# Sheet1.net
KiCad netlist of a schematic drawn in Altium Designer
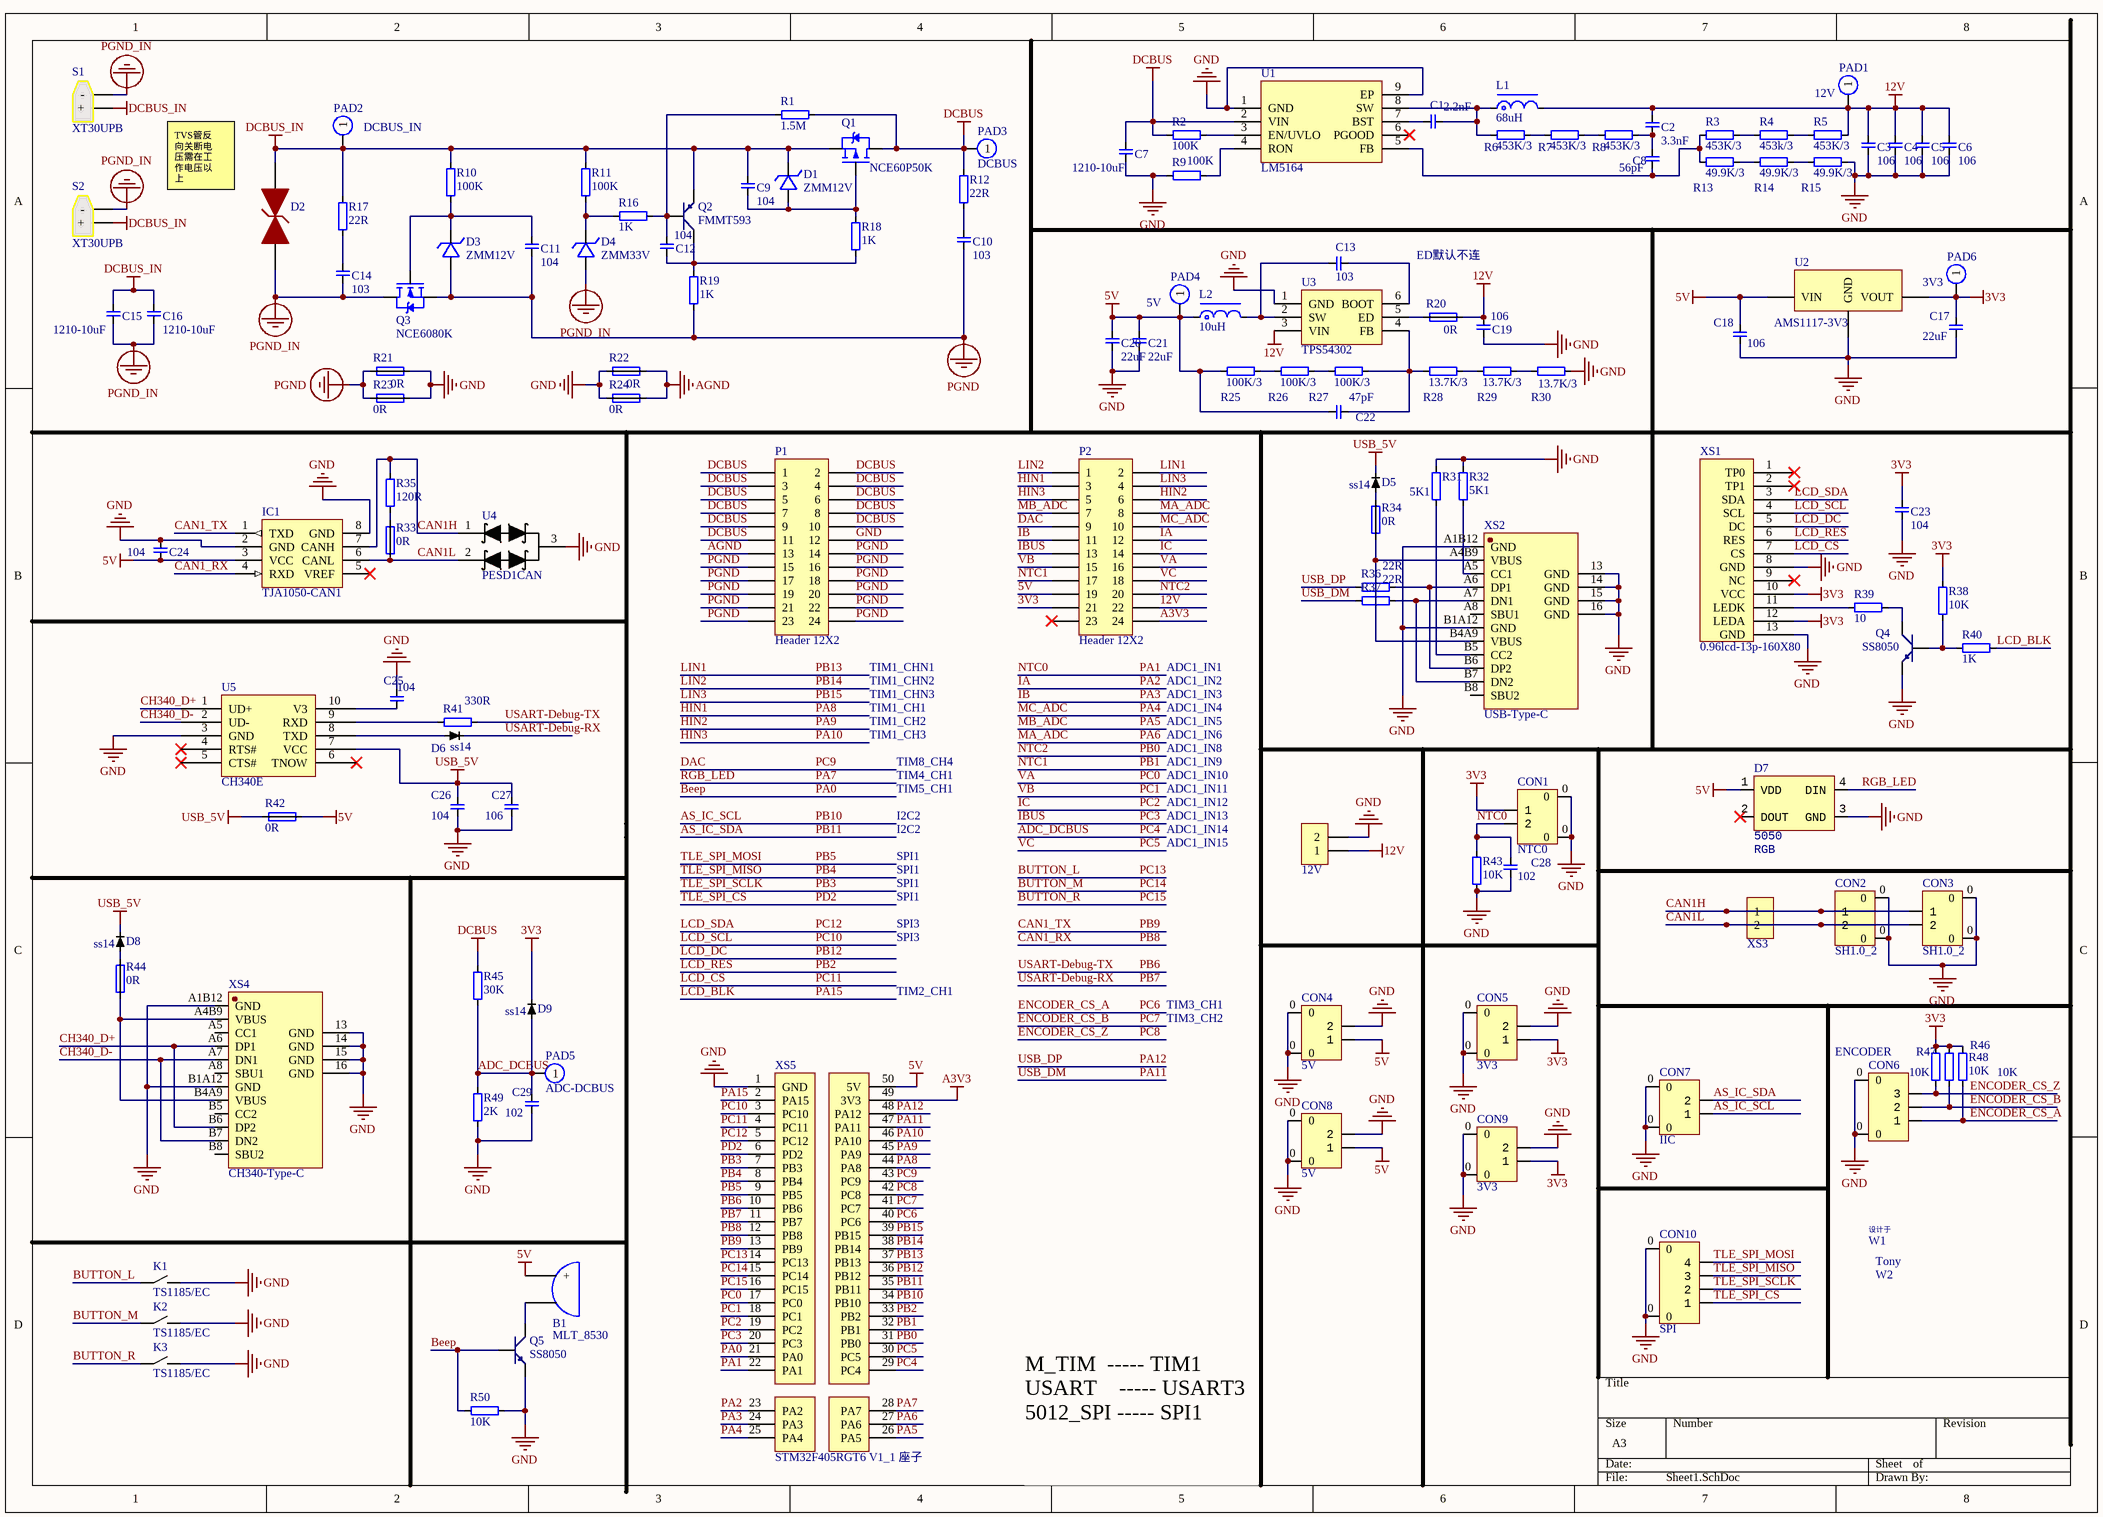
[diagram p0: Sheet1.SchDoc]

(export (version "E")
  (design (tool "Eeschema 10.0.6"))
  (components
    (comp (ref "12V")
      (value "HDR-1X2")
      (footprint "15EDGVM-2P")
      (description "2P接插件")
      (fields (field (name "版权归属") "源创客"))
      (libsource (lib "") (part "Header 2_1"))
    )
    (comp (ref "B1") (value "MLT_8530") (footprint "BEEP-8530") (libsource (lib "基本元件库") (part "Beep")))
    (comp (ref "C1") (value "2.2nF") (footprint "CAP_0603") (libsource (lib "基本元件库") (part "cap")))
    (comp (ref "C2") (value "3.3nF") (footprint "CAP_0603") (libsource (lib "基本元件库") (part "cap")))
    (comp (ref "C3") (value "106") (footprint "CAP_0603") (libsource (lib "基本元件库") (part "cap")))
    (comp (ref "C4") (value "106") (footprint "CAP_0603") (libsource (lib "基本元件库") (part "cap")))
    (comp (ref "C5") (value "106") (footprint "CAP_0603") (libsource (lib "基本元件库") (part "cap")))
    (comp (ref "C6") (value "106") (footprint "CAP_0603") (libsource (lib "基本元件库") (part "cap")))
    (comp (ref "C7") (value "1210-10uF") (footprint "CAP_1210_L") (libsource (lib "基本元件库") (part "cap")))
    (comp (ref "C8") (value "56pF") (footprint "CAP_0603") (libsource (lib "基本元件库") (part "cap")))
    (comp (ref "C9") (value "104") (footprint "CAP_0603") (libsource (lib "基本元件库") (part "cap")))
    (comp (ref "C10") (value "103") (footprint "CAP_0603") (libsource (lib "基本元件库") (part "cap")))
    (comp (ref "C11") (value "104") (footprint "CAP_0603") (libsource (lib "基本元件库") (part "cap")))
    (comp (ref "C12") (value "104") (footprint "CAP_0603") (libsource (lib "基本元件库") (part "cap")))
    (comp (ref "C13") (value "103") (footprint "CAP_0603") (libsource (lib "基本元件库") (part "cap")))
    (comp (ref "C14") (value "103") (footprint "CAP_0603") (libsource (lib "基本元件库") (part "cap")))
    (comp (ref "C15") (value "1210-10uF") (footprint "CAP_1210_L") (libsource (lib "基本元件库") (part "cap")))
    (comp (ref "C16") (value "1210-10uF") (footprint "CAP_1210_L") (libsource (lib "基本元件库") (part "cap")))
    (comp (ref "C17") (value "22uF") (footprint "CAP_0603") (libsource (lib "基本元件库") (part "cap")))
    (comp (ref "C18") (value "106") (footprint "CAP_0603") (libsource (lib "基本元件库") (part "cap")))
    (comp (ref "C19") (value "106") (footprint "CAP_0603") (libsource (lib "基本元件库") (part "cap")))
    (comp (ref "C20") (value "22uF") (footprint "CAP_0603") (libsource (lib "基本元件库") (part "cap")))
    (comp (ref "C21") (value "22uF") (footprint "CAP_0603") (libsource (lib "基本元件库") (part "cap")))
    (comp (ref "C22") (value "47pF") (footprint "CAP_0603") (libsource (lib "基本元件库") (part "cap")))
    (comp (ref "C23") (value "104") (footprint "CAP_0603") (libsource (lib "基本元件库") (part "cap")))
    (comp (ref "C24") (value "104") (footprint "CAP_0603") (libsource (lib "基本元件库") (part "cap")))
    (comp (ref "C25") (value "104") (footprint "CAP_0603") (libsource (lib "基本元件库") (part "cap")))
    (comp (ref "C26") (value "104") (footprint "CAP_0603") (libsource (lib "基本元件库") (part "cap")))
    (comp (ref "C27") (value "106") (footprint "CAP_0603") (libsource (lib "基本元件库") (part "cap")))
    (comp (ref "C28") (value "102") (footprint "CAP_0603") (libsource (lib "基本元件库") (part "cap")))
    (comp (ref "C29") (value "102") (footprint "CAP_0603") (libsource (lib "基本元件库") (part "cap")))
    (comp (ref "CON1")
      (value "NTC0")
      (footprint "PH2.0-LS-2P")
      (description "PH2.0_2 座子")
      (libsource (lib "接插件库") (part "PH2.0_2"))
    )
    (comp (ref "CON2")
      (value "SH1.0_2")
      (footprint "SH1.0 LS 2P")
      (description "SH1.0 座子")
      (libsource (lib "接插件库") (part "SH1.0_2"))
    )
    (comp (ref "CON3")
      (value "SH1.0_2")
      (footprint "SH1.0 LS 2P")
      (description "SH1.0 座子")
      (libsource (lib "接插件库") (part "SH1.0_2"))
    )
    (comp (ref "CON4")
      (value "5V")
      (footprint "XH2.54-LS-2P")
      (description "XH2.54_2 座子")
      (libsource (lib "接插件库") (part "XH2.54_2"))
    )
    (comp (ref "CON5")
      (value "3V3")
      (footprint "ZH1.5-LS-2P")
      (description "ZH1.5_2 座子")
      (libsource (lib "接插件库") (part "ZH1.5_2"))
    )
    (comp (ref "CON6")
      (value "ENCODER")
      (footprint "PH2.0-LS-3P")
      (description "PH2.0 座子")
      (libsource (lib "接插件库") (part "PH2.0_3"))
    )
    (comp (ref "CON7")
      (value "IIC")
      (footprint "PH2.0-LS-2P")
      (description "PH2.0_2 座子")
      (libsource (lib "") (part "PH2.0_2_1"))
    )
    (comp (ref "CON8")
      (value "5V")
      (footprint "XH2.54-LS-2P")
      (description "XH2.54_2 座子")
      (libsource (lib "接插件库") (part "XH2.54_2"))
    )
    (comp (ref "CON9")
      (value "3V3")
      (footprint "ZH1.5-LS-2P")
      (description "ZH1.5_2 座子")
      (libsource (lib "接插件库") (part "ZH1.5_2"))
    )
    (comp (ref "CON10")
      (value "SPI")
      (footprint "SH1.0 LS 4P")
      (description "SH1.0 座子")
      (libsource (lib "接插件库") (part "SH1.0_4"))
    )
    (comp (ref "D1")
      (value "ZMM12V")
      (footprint "LL-34")
      (description "Zener Diodes 稳压二极管")
      (libsource (lib "基本元件库") (part "ZD"))
    )
    (comp (ref "D2")
      (value "SMBJ28CA")
      (footprint "SMB(DO-211AA)")
      (description "瞬态电压抑制二极管(TVS) 钳位二极管")
      (libsource (lib "基本元件库") (part "TVS"))
    )
    (comp (ref "D3")
      (value "ZMM12V")
      (footprint "LL-34")
      (description "Zener Diodes 稳压二极管")
      (libsource (lib "基本元件库") (part "ZD"))
    )
    (comp (ref "D4")
      (value "ZMM33V")
      (footprint "LL-34")
      (description "Zener Diodes 稳压二极管")
      (libsource (lib "基本元件库") (part "ZD"))
    )
    (comp (ref "D5") (value "ss14") (footprint "SOD-323") (libsource (lib "基本元件库") (part "Diode")))
    (comp (ref "D6") (value "ss14") (footprint "SOD-323") (libsource (lib "") (part "Diode_1")))
    (comp (ref "D7")
      (value "RGB")
      (footprint "LED_5050_WS2812B")
      (description "LED")
      (fields (field (name "TYPE") "5050"))
      (libsource (lib "基本元件库") (part "RGB_4WIC"))
    )
    (comp (ref "D8") (value "ss14") (footprint "SOD-323") (libsource (lib "基本元件库") (part "Diode")))
    (comp (ref "D9") (value "ss14") (footprint "SOD-323") (libsource (lib "基本元件库") (part "Diode")))
    (comp (ref "IC1")
      (value "TJA1050-CAN1")
      (footprint "SOP8_N")
      (description "CAN总线收发芯片")
      (fields (field (name "版权归属") "源创客"))
      (libsource (lib "IC") (part "TJA1050"))
    )
    (comp (ref "K1")
      (value "TS1185/EC")
      (footprint "TS-1185EC-X-X-X")
      (description "3*4*2 立贴轻触开关 2Pin/4Pin")
      (libsource (lib "基本元件库") (part "Button-LT-3040"))
    )
    (comp (ref "K2")
      (value "TS1185/EC")
      (footprint "TS-1185EC-X-X-X")
      (description "3*4*2 立贴轻触开关 2Pin/4Pin")
      (libsource (lib "基本元件库") (part "Button-LT-3040"))
    )
    (comp (ref "K3")
      (value "TS1185/EC")
      (footprint "TS-1185EC-X-X-X")
      (description "3*4*2 立贴轻触开关 2Pin/4Pin")
      (libsource (lib "基本元件库") (part "Button-LT-3040"))
    )
    (comp (ref "L1") (value "68uH") (footprint "NR4030") (libsource (lib "基本元件库") (part "INDUCTOR")))
    (comp (ref "L2") (value "10uH") (footprint "NR3015") (libsource (lib "基本元件库") (part "INDUCTOR")))
    (comp (ref "P1")
      (value "Header 12X2")
      (footprint "HDR2X12")
      (description "Header, 12-Pin, Dual row")
      (fields (field (name "PUBLISHER") "Altium Limited"))
      (libsource (lib "Miscellaneous Connectors") (part "Header 12X2"))
    )
    (comp (ref "P2")
      (value "Header 12X2")
      (footprint "HDR2X12")
      (description "Header, 12-Pin, Dual row")
      (fields (field (name "PUBLISHER") "Altium Limited"))
      (libsource (lib "Miscellaneous Connectors") (part "Header 12X2"))
    )
    (comp (ref "PAD1")
      (value "12V")
      (footprint "PAD-1")
      (description "50mil单点焊盘，用于测试")
      (libsource (lib "基本元件库") (part "PAD"))
    )
    (comp (ref "PAD2")
      (value "DCBUS_IN")
      (footprint "PAD-1")
      (description "50mil单点焊盘，用于测试")
      (libsource (lib "基本元件库") (part "PAD"))
    )
    (comp (ref "PAD3")
      (value "DCBUS")
      (footprint "PAD-1")
      (description "50mil单点焊盘，用于测试")
      (libsource (lib "基本元件库") (part "PAD"))
    )
    (comp (ref "PAD4")
      (value "5V")
      (footprint "PAD-1")
      (description "50mil单点焊盘，用于测试")
      (libsource (lib "基本元件库") (part "PAD"))
    )
    (comp (ref "PAD5")
      (value "ADC-DCBUS")
      (footprint "PAD-1")
      (description "50mil单点焊盘，用于测试")
      (libsource (lib "基本元件库") (part "PAD"))
    )
    (comp (ref "PAD6")
      (value "3V3")
      (footprint "PAD-1")
      (description "50mil单点焊盘，用于测试")
      (libsource (lib "基本元件库") (part "PAD"))
    )
    (comp (ref "Q1")
      (value "NCE60P50K")
      (footprint "TO252-2")
      (description "N沟道MOSFIT\r\n-NCE60P50K-TO252-2")
      (libsource (lib "基本元件库") (part "PMOS"))
    )
    (comp (ref "Q2") (value "FMMT593") (footprint "SOT23") (libsource (lib "基本元件库") (part "PNP")))
    (comp (ref "Q3")
      (value "NCE6080K")
      (footprint "TO252-2")
      (description "N沟道MOSFIT\r\n-NCE6080K-TO252-2")
      (libsource (lib "基本元件库") (part "NMOS"))
    )
    (comp (ref "Q4") (value "SS8050") (footprint "SOT23") (libsource (lib "基本元件库") (part "NPN")))
    (comp (ref "Q5") (value "SS8050") (footprint "SOT23") (libsource (lib "基本元件库") (part "NPN")))
    (comp (ref "R1") (value "1.5M") (footprint "RES_0603") (libsource (lib "基本元件库") (part "Res")))
    (comp (ref "R2") (value "100K") (footprint "RES_0603") (libsource (lib "基本元件库") (part "Res")))
    (comp (ref "R3") (value "453K/3") (footprint "RES_0603") (libsource (lib "基本元件库") (part "Res")))
    (comp (ref "R4") (value "453k/3") (footprint "RES_0603") (libsource (lib "基本元件库") (part "Res")))
    (comp (ref "R5") (value "453K/3") (footprint "RES_0603") (libsource (lib "基本元件库") (part "Res")))
    (comp (ref "R6") (value "453K/3") (footprint "RES_0603") (libsource (lib "基本元件库") (part "Res")))
    (comp (ref "R7") (value "453K/3") (footprint "RES_0603") (libsource (lib "基本元件库") (part "Res")))
    (comp (ref "R8") (value "453K/3") (footprint "RES_0603") (libsource (lib "基本元件库") (part "Res")))
    (comp (ref "R9") (value "100K") (footprint "RES_0603") (libsource (lib "基本元件库") (part "Res")))
    (comp (ref "R10") (value "100K") (footprint "RES_0603") (libsource (lib "基本元件库") (part "Res")))
    (comp (ref "R11") (value "100K") (footprint "RES_0603") (libsource (lib "基本元件库") (part "Res")))
    (comp (ref "R12") (value "22R") (footprint "RES_0603") (libsource (lib "基本元件库") (part "Res")))
    (comp (ref "R13") (value "49.9K/3") (footprint "RES_0603") (libsource (lib "基本元件库") (part "Res")))
    (comp (ref "R14") (value "49.9K/3") (footprint "RES_0603") (libsource (lib "基本元件库") (part "Res")))
    (comp (ref "R15") (value "49.9K/3") (footprint "RES_0603") (libsource (lib "基本元件库") (part "Res")))
    (comp (ref "R16") (value "1K") (footprint "RES_0603") (libsource (lib "基本元件库") (part "Res")))
    (comp (ref "R17") (value "22R") (footprint "RES_0603") (libsource (lib "基本元件库") (part "Res")))
    (comp (ref "R18") (value "1K") (footprint "RES_0603") (libsource (lib "基本元件库") (part "Res")))
    (comp (ref "R19") (value "1K") (footprint "RES_0603") (libsource (lib "基本元件库") (part "Res")))
    (comp (ref "R20") (value "0R") (footprint "RES_0805-SHORT") (libsource (lib "基本元件库") (part "Res-SHORT")))
    (comp (ref "R21") (value "0R") (footprint "RES_0805-SHORT") (libsource (lib "基本元件库") (part "Res-SHORT")))
    (comp (ref "R22") (value "0R") (footprint "RES_0805-SHORT") (libsource (lib "基本元件库") (part "Res-SHORT")))
    (comp (ref "R23") (value "0R") (footprint "RES_0805-SHORT") (libsource (lib "基本元件库") (part "Res-SHORT")))
    (comp (ref "R24") (value "0R") (footprint "RES_0805-SHORT") (libsource (lib "基本元件库") (part "Res-SHORT")))
    (comp (ref "R25") (value "100K/3") (footprint "RES_0603") (libsource (lib "基本元件库") (part "Res")))
    (comp (ref "R26") (value "100K/3") (footprint "RES_0603") (libsource (lib "基本元件库") (part "Res")))
    (comp (ref "R27") (value "100K/3") (footprint "RES_0603") (libsource (lib "基本元件库") (part "Res")))
    (comp (ref "R28") (value "13.7K/3") (footprint "RES_0603") (libsource (lib "基本元件库") (part "Res")))
    (comp (ref "R29") (value "13.7K/3") (footprint "RES_0603") (libsource (lib "基本元件库") (part "Res")))
    (comp (ref "R30") (value "13.7K/3") (footprint "RES_0603") (libsource (lib "基本元件库") (part "Res")))
    (comp (ref "R31") (value "5K1") (footprint "RES_0603") (libsource (lib "基本元件库") (part "Res")))
    (comp (ref "R32") (value "5K1") (footprint "RES_0603") (libsource (lib "基本元件库") (part "Res")))
    (comp (ref "R33") (value "0R") (footprint "RES_0805-SHORT") (libsource (lib "基本元件库") (part "Res-SHORT")))
    (comp (ref "R34") (value "0R") (footprint "RES_0805-SHORT") (libsource (lib "基本元件库") (part "Res-SHORT")))
    (comp (ref "R35") (value "120R") (footprint "RES_0603") (libsource (lib "基本元件库") (part "Res")))
    (comp (ref "R36") (value "22R") (footprint "RES_0603") (libsource (lib "基本元件库") (part "Res")))
    (comp (ref "R37") (value "22R") (footprint "RES_0603") (libsource (lib "基本元件库") (part "Res")))
    (comp (ref "R38") (value "10K") (footprint "RES_0603") (libsource (lib "基本元件库") (part "Res")))
    (comp (ref "R39") (value "10") (footprint "RES_0603") (libsource (lib "基本元件库") (part "Res")))
    (comp (ref "R40") (value "1K") (footprint "RES_0603") (libsource (lib "基本元件库") (part "Res")))
    (comp (ref "R41") (value "330R") (footprint "RES_0603") (libsource (lib "基本元件库") (part "Res")))
    (comp (ref "R42") (value "0R") (footprint "RES_0805-SHORT") (libsource (lib "基本元件库") (part "Res-SHORT")))
    (comp (ref "R43") (value "10K") (footprint "RES_0603") (libsource (lib "基本元件库") (part "Res")))
    (comp (ref "R44") (value "0R") (footprint "RES_0805-SHORT") (libsource (lib "基本元件库") (part "Res-SHORT")))
    (comp (ref "R45") (value "30K") (footprint "RES_0603") (libsource (lib "基本元件库") (part "Res")))
    (comp (ref "R46") (value "10K") (footprint "RES_0603") (libsource (lib "基本元件库") (part "Res")))
    (comp (ref "R47") (value "10K") (footprint "RES_0603") (libsource (lib "基本元件库") (part "Res")))
    (comp (ref "R48") (value "10K") (footprint "RES_0603") (libsource (lib "基本元件库") (part "Res")))
    (comp (ref "R49") (value "2K") (footprint "RES_0603") (libsource (lib "基本元件库") (part "Res")))
    (comp (ref "R50") (value "10K") (footprint "RES_0603") (libsource (lib "基本元件库") (part "Res")))
    (comp (ref "S1")
      (value "XT30UPB")
      (footprint "XT30UPB-M")
      (description "XT30UPB-I/O")
      (libsource (lib "SOURCE") (part "XT30UPB"))
    )
    (comp (ref "S2")
      (value "XT30UPB")
      (footprint "XT30UPB-F")
      (description "XT30UPB-I/O")
      (libsource (lib "SOURCE") (part "XT30UPB"))
    )
    (comp (ref "U1")
      (value "LM5164")
      (footprint "SOP-8")
      (description "DC-DC芯片")
      (libsource (lib "SOURCE") (part "LM5164"))
    )
    (comp (ref "U2") (value "AMS1117-3V3") (footprint "SOT223") (libsource (lib "SOURCE") (part "AMS1117")))
    (comp (ref "U3")
      (value "TPS54302")
      (footprint "SOT23-6")
      (description "12V稳压5VDCDC")
      (libsource (lib "SOURCE") (part "TPS54302"))
    )
    (comp (ref "U4")
      (value "PESD1CAN")
      (footprint "SOT23-3")
      (description "CAN过压保护,放于外部接口端")
      (libsource (lib "IC") (part "PESD1CAN"))
    )
    (comp (ref "U5")
      (value "CH340E")
      (footprint "MSOP10")
      (description "USB转串口 无外置晶振")
      (libsource (lib "IC") (part "CH340E"))
    )
    (comp (ref "W1") (value "设计于") (footprint "designed by（430-70）") (libsource (lib "丝印库") (part "设计于")))
    (comp (ref "W2") (value "Tony") (footprint "Tony_2(200-70)") (libsource (lib "丝印库") (part "Tony")))
    (comp (ref "XS1")
      (value "0.96lcd-13p-160X80")
      (footprint "LCD 0.96-13p")
      (description "焊接屏幕")
      (libsource (lib "第一次绘制库") (part "0.96lcd-13p"))
    )
    (comp (ref "XS2")
      (value "USB-Type-C")
      (footprint "TypeC-304-16BCP")
      (libsource (lib "接插件库") (part "Type-C母口"))
    )
    (comp (ref "XS3")
      (value "HDR-1X2")
      (footprint "15EDGVM-2P")
      (description "2P接插件")
      (fields (field (name "版权归属") "源创客"))
      (libsource (lib "接插件库") (part "Header 2"))
    )
    (comp (ref "XS4")
      (value "CH340-Type-C")
      (footprint "TypeC-304-16BCP")
      (libsource (lib "接插件库") (part "Type-C母口"))
    )
    (comp (ref "XS5")
      (value "STM32F405RGT6 V1_1 座子")
      (footprint "STM32F405RGT6 V1_1座子")
      (libsource (lib "第一次绘制库") (part "STM32F405RGT6 V1_1 座子"))
    )
  )
  (nets
    (net (code "1") (name "/ADC_DCBUS") (class "Default")
      (node (ref "C29") (pin "2") (pinfunction "2_2") (pintype "passive"))
      (node (ref "D9") (pin "1") (pintype "passive"))
      (node (ref "PAD5") (pin "1") (pinfunction "1_1") (pintype "passive"))
      (node (ref "R45") (pin "1") (pinfunction "1_1") (pintype "passive"))
      (node (ref "R49") (pin "2") (pinfunction "2_2") (pintype "passive"))
      (node (ref "XS5") (pin "29") (pinfunction "PC4_29") (pintype "passive"))
    )
    (net (code "2") (name "/AS_IC_SCL") (class "Default")
      (node (ref "CON7") (pin "1") (pinfunction "1_1") (pintype "passive"))
      (node (ref "XS5") (pin "34") (pinfunction "PB10_34") (pintype "passive"))
    )
    (net (code "3") (name "/AS_IC_SDA") (class "Default")
      (node (ref "CON7") (pin "2") (pinfunction "2_2") (pintype "passive"))
      (node (ref "XS5") (pin "35") (pinfunction "PB11_35") (pintype "passive"))
    )
    (net (code "4") (name "/BUTTON_L") (class "Default")
      (node (ref "K1") (pin "1") (pinfunction "1_1") (pintype "passive"))
      (node (ref "XS5") (pin "14") (pinfunction "PC13_14") (pintype "passive"))
    )
    (net (code "5") (name "/BUTTON_M") (class "Default")
      (node (ref "K2") (pin "1") (pinfunction "1_1") (pintype "passive"))
      (node (ref "XS5") (pin "15") (pinfunction "PC14_15") (pintype "passive"))
    )
    (net (code "6") (name "/BUTTON_R") (class "Default")
      (node (ref "K3") (pin "1") (pinfunction "1_1") (pintype "passive"))
      (node (ref "XS5") (pin "16") (pinfunction "PC15_16") (pintype "passive"))
    )
    (net (code "7") (name "/Beep") (class "Default")
      (node (ref "Q5") (pin "1") (pinfunction "B_1") (pintype "passive"))
      (node (ref "R50") (pin "2") (pinfunction "2_2") (pintype "passive"))
      (node (ref "XS5") (pin "21") (pinfunction "PA0_21") (pintype "passive"))
    )
    (net (code "8") (name "/CAN1H") (class "Default")
      (node (ref "CON2") (pin "1") (pinfunction "1_1") (pintype "passive"))
      (node (ref "CON3") (pin "1") (pinfunction "1_1") (pintype "passive"))
      (node (ref "IC1") (pin "7") (pinfunction "CANH_7") (pintype "passive"))
      (node (ref "R35") (pin "2") (pinfunction "2_2") (pintype "passive"))
      (node (ref "U4") (pin "1") (pinfunction "1_1") (pintype "passive"))
      (node (ref "XS3") (pin "1") (pinfunction "1_1") (pintype "passive"))
    )
    (net (code "9") (name "/CAN1L") (class "Default")
      (node (ref "CON2") (pin "2") (pinfunction "2_2") (pintype "passive"))
      (node (ref "CON3") (pin "2") (pinfunction "2_2") (pintype "passive"))
      (node (ref "IC1") (pin "6") (pinfunction "CANL_6") (pintype "passive"))
      (node (ref "R33") (pin "2") (pinfunction "2_2") (pintype "passive"))
      (node (ref "U4") (pin "2") (pinfunction "2_2") (pintype "passive"))
      (node (ref "XS3") (pin "2") (pinfunction "2_2") (pintype "passive"))
    )
    (net (code "10") (name "/CAN1_RX") (class "Default")
      (node (ref "IC1") (pin "4") (pinfunction "RXD_4") (pintype "input"))
      (node (ref "XS5") (pin "12") (pinfunction "PB8_12") (pintype "passive"))
    )
    (net (code "11") (name "/CAN1_TX") (class "Default")
      (node (ref "IC1") (pin "1") (pinfunction "TXD_1") (pintype "output"))
      (node (ref "XS5") (pin "13") (pinfunction "PB9_13") (pintype "passive"))
    )
    (net (code "12") (name "/CH340_D+") (class "Default")
      (node (ref "U5") (pin "1") (pinfunction "UD+_1") (pintype "passive"))
      (node (ref "XS4") (pin "A6") (pinfunction "DP1_A6") (pintype "passive"))
      (node (ref "XS4") (pin "B6") (pinfunction "DP2_B6") (pintype "passive"))
    )
    (net (code "13") (name "/CH340_D-") (class "Default")
      (node (ref "U5") (pin "2") (pinfunction "UD-_2") (pintype "passive"))
      (node (ref "XS4") (pin "A7") (pinfunction "DN1_A7") (pintype "passive"))
      (node (ref "XS4") (pin "B7") (pinfunction "DN2_B7") (pintype "passive"))
    )
    (net (code "14") (name "/DAC") (class "Default")
      (node (ref "P2") (pin "9") (pinfunction "9_9") (pintype "passive"))
      (node (ref "XS5") (pin "43") (pinfunction "PC9_43") (pintype "passive"))
    )
    (net (code "15") (name "/ENCODER_CS_A") (class "Default")
      (node (ref "CON6") (pin "1") (pinfunction "1_1") (pintype "passive"))
      (node (ref "R48") (pin "2") (pinfunction "2_2") (pintype "passive"))
      (node (ref "XS5") (pin "40") (pinfunction "PC6_40") (pintype "passive"))
    )
    (net (code "16") (name "/ENCODER_CS_B") (class "Default")
      (node (ref "CON6") (pin "2") (pinfunction "2_2") (pintype "passive"))
      (node (ref "R46") (pin "2") (pinfunction "2_2") (pintype "passive"))
      (node (ref "XS5") (pin "41") (pinfunction "PC7_41") (pintype "passive"))
    )
    (net (code "17") (name "/ENCODER_CS_Z") (class "Default")
      (node (ref "CON6") (pin "3") (pinfunction "3_3") (pintype "passive"))
      (node (ref "R47") (pin "2") (pinfunction "2_2") (pintype "passive"))
      (node (ref "XS5") (pin "42") (pinfunction "PC8_42") (pintype "passive"))
    )
    (net (code "18") (name "/HIN1") (class "Default")
      (node (ref "P2") (pin "3") (pinfunction "3_3") (pintype "passive"))
      (node (ref "XS5") (pin "44") (pinfunction "PA8_44") (pintype "passive"))
    )
    (net (code "19") (name "/HIN2") (class "Default")
      (node (ref "P2") (pin "6") (pinfunction "6_6") (pintype "passive"))
      (node (ref "XS5") (pin "45") (pinfunction "PA9_45") (pintype "passive"))
    )
    (net (code "20") (name "/HIN3") (class "Default")
      (node (ref "P2") (pin "5") (pinfunction "5_5") (pintype "passive"))
      (node (ref "XS5") (pin "46") (pinfunction "PA10_46") (pintype "passive"))
    )
    (net (code "21") (name "/IA") (class "Default")
      (node (ref "P2") (pin "12") (pinfunction "12_12") (pintype "passive"))
      (node (ref "XS5") (pin "23") (pinfunction "PA2_23") (pintype "passive"))
    )
    (net (code "22") (name "/IB") (class "Default")
      (node (ref "P2") (pin "11") (pinfunction "11_11") (pintype "passive"))
      (node (ref "XS5") (pin "24") (pinfunction "PA3_24") (pintype "passive"))
    )
    (net (code "23") (name "/IBUS") (class "Default")
      (node (ref "P2") (pin "13") (pinfunction "13_13") (pintype "passive"))
      (node (ref "XS5") (pin "20") (pinfunction "PC3_20") (pintype "passive"))
    )
    (net (code "24") (name "/IC") (class "Default")
      (node (ref "P2") (pin "14") (pinfunction "14_14") (pintype "passive"))
      (node (ref "XS5") (pin "19") (pinfunction "PC2_19") (pintype "passive"))
    )
    (net (code "25") (name "/LCD_BLK") (class "Default")
      (node (ref "R40") (pin "2") (pinfunction "2_2") (pintype "passive"))
      (node (ref "XS5") (pin "2") (pinfunction "PA15_2") (pintype "passive"))
    )
    (net (code "26") (name "/LCD_CS") (class "Default")
      (node (ref "XS1") (pin "7") (pinfunction "CS_7") (pintype "passive"))
      (node (ref "XS5") (pin "4") (pinfunction "PC11_4") (pintype "passive"))
    )
    (net (code "27") (name "/LCD_DC") (class "Default")
      (node (ref "XS1") (pin "5") (pinfunction "DC_5") (pintype "passive"))
      (node (ref "XS5") (pin "36") (pinfunction "PB12_36") (pintype "passive"))
    )
    (net (code "28") (name "/LCD_RES") (class "Default")
      (node (ref "XS1") (pin "6") (pinfunction "RES_6") (pintype "passive"))
      (node (ref "XS5") (pin "33") (pinfunction "PB2_33") (pintype "passive"))
    )
    (net (code "29") (name "/LCD_SCL") (class "Default")
      (node (ref "XS1") (pin "4") (pinfunction "SCL_4") (pintype "passive"))
      (node (ref "XS5") (pin "3") (pinfunction "PC10_3") (pintype "passive"))
    )
    (net (code "30") (name "/LCD_SDA") (class "Default")
      (node (ref "XS1") (pin "3") (pinfunction "SDA_3") (pintype "passive"))
      (node (ref "XS5") (pin "5") (pinfunction "PC12_5") (pintype "passive"))
    )
    (net (code "31") (name "/LIN1") (class "Default")
      (node (ref "P2") (pin "2") (pinfunction "2_2") (pintype "passive"))
      (node (ref "XS5") (pin "37") (pinfunction "PB13_37") (pintype "passive"))
    )
    (net (code "32") (name "/LIN2") (class "Default")
      (node (ref "P2") (pin "1") (pinfunction "1_1") (pintype "passive"))
      (node (ref "XS5") (pin "38") (pinfunction "PB14_38") (pintype "passive"))
    )
    (net (code "33") (name "/LIN3") (class "Default")
      (node (ref "P2") (pin "4") (pinfunction "4_4") (pintype "passive"))
      (node (ref "XS5") (pin "39") (pinfunction "PB15_39") (pintype "passive"))
    )
    (net (code "34") (name "/MA_ADC") (class "Default")
      (node (ref "P2") (pin "8") (pinfunction "8_8") (pintype "passive"))
      (node (ref "XS5") (pin "27") (pinfunction "PA6_27") (pintype "passive"))
    )
    (net (code "35") (name "/MB_ADC") (class "Default")
      (node (ref "P2") (pin "7") (pinfunction "7_7") (pintype "passive"))
      (node (ref "XS5") (pin "26") (pinfunction "PA5_26") (pintype "passive"))
    )
    (net (code "36") (name "/MC_ADC") (class "Default")
      (node (ref "P2") (pin "10") (pinfunction "10_10") (pintype "passive"))
      (node (ref "XS5") (pin "25") (pinfunction "PA4_25") (pintype "passive"))
    )
    (net (code "37") (name "/NTC0") (class "Default")
      (node (ref "C28") (pin "2") (pinfunction "2_2") (pintype "passive"))
      (node (ref "CON1") (pin "2") (pinfunction "2_2") (pintype "passive"))
      (node (ref "R43") (pin "1") (pinfunction "1_1") (pintype "passive"))
      (node (ref "XS5") (pin "22") (pinfunction "PA1_22") (pintype "passive"))
    )
    (net (code "38") (name "/NTC1") (class "Default")
      (node (ref "P2") (pin "17") (pinfunction "17_17") (pintype "passive"))
      (node (ref "XS5") (pin "32") (pinfunction "PB1_32") (pintype "passive"))
    )
    (net (code "39") (name "/NTC2") (class "Default")
      (node (ref "P2") (pin "20") (pinfunction "20_20") (pintype "passive"))
      (node (ref "XS5") (pin "31") (pinfunction "PB0_31") (pintype "passive"))
    )
    (net (code "40") (name "/PA7") (class "Default")
      (node (ref "D7") (pin "4") (pinfunction "DIN_4") (pintype "passive"))
      (node (ref "XS5") (pin "28") (pinfunction "PA7_28") (pintype "passive"))
    )
    (net (code "41") (name "/PA11") (class "Default")
      (node (ref "R37") (pin "1") (pinfunction "1_1") (pintype "passive"))
      (node (ref "XS5") (pin "47") (pinfunction "PA11_47") (pintype "passive"))
    )
    (net (code "42") (name "/PA12") (class "Default")
      (node (ref "R36") (pin "1") (pinfunction "1_1") (pintype "passive"))
      (node (ref "XS5") (pin "48") (pinfunction "PA12_48") (pintype "passive"))
    )
    (net (code "43") (name "/PB3") (class "Default")
      (node (ref "CON10") (pin "2") (pinfunction "2_2") (pintype "passive"))
      (node (ref "XS5") (pin "7") (pinfunction "PB3_7") (pintype "passive"))
    )
    (net (code "44") (name "/PB4") (class "Default")
      (node (ref "CON10") (pin "3") (pinfunction "3_3") (pintype "passive"))
      (node (ref "XS5") (pin "8") (pinfunction "PB4_8") (pintype "passive"))
    )
    (net (code "45") (name "/PB5") (class "Default")
      (node (ref "CON10") (pin "4") (pinfunction "4_4") (pintype "passive"))
      (node (ref "XS5") (pin "9") (pinfunction "PB5_9") (pintype "passive"))
    )
    (net (code "46") (name "/PB6") (class "Default")
      (node (ref "R41") (pin "2") (pinfunction "2_2") (pintype "passive"))
      (node (ref "XS5") (pin "10") (pinfunction "PB6_10") (pintype "passive"))
    )
    (net (code "47") (name "/PB7") (class "Default")
      (node (ref "D6") (pin "1") (pintype "passive"))
      (node (ref "XS5") (pin "11") (pinfunction "PB7_11") (pintype "passive"))
    )
    (net (code "48") (name "/PC0") (class "Default")
      (node (ref "P2") (pin "16") (pinfunction "16_16") (pintype "passive"))
      (node (ref "XS5") (pin "17") (pinfunction "PC0_17") (pintype "passive"))
    )
    (net (code "49") (name "/PC1") (class "Default")
      (node (ref "P2") (pin "15") (pinfunction "15_15") (pintype "passive"))
      (node (ref "XS5") (pin "18") (pinfunction "PC1_18") (pintype "passive"))
    )
    (net (code "50") (name "/PC5") (class "Default")
      (node (ref "P2") (pin "18") (pinfunction "18_18") (pintype "passive"))
      (node (ref "XS5") (pin "30") (pinfunction "PC5_30") (pintype "passive"))
    )
    (net (code "51") (name "/PD2") (class "Default")
      (node (ref "CON10") (pin "1") (pinfunction "1_1") (pintype "passive"))
      (node (ref "XS5") (pin "6") (pinfunction "PD2_6") (pintype "passive"))
    )
    (net (code "52") (name "3V3") (class "Default")
      (node (ref "C17") (pin "2") (pinfunction "2_2") (pintype "passive"))
      (node (ref "C23") (pin "2") (pinfunction "2_2") (pintype "passive"))
      (node (ref "CON1") (pin "1") (pinfunction "1_1") (pintype "passive"))
      (node (ref "CON5") (pin "1") (pinfunction "1_1") (pintype "passive"))
      (node (ref "CON9") (pin "1") (pinfunction "1_1") (pintype "passive"))
      (node (ref "D9") (pin "2") (pintype "passive"))
      (node (ref "P2") (pin "21") (pinfunction "21_21") (pintype "passive"))
      (node (ref "PAD6") (pin "1") (pinfunction "1_1") (pintype "passive"))
      (node (ref "R38") (pin "1") (pinfunction "1_1") (pintype "passive"))
      (node (ref "R46") (pin "1") (pinfunction "1_1") (pintype "passive"))
      (node (ref "R47") (pin "1") (pinfunction "1_1") (pintype "passive"))
      (node (ref "R48") (pin "1") (pinfunction "1_1") (pintype "passive"))
      (node (ref "U2") (pin "2") (pinfunction "VOUT_2") (pintype "passive"))
      (node (ref "XS1") (pin "10") (pinfunction "VCC_10") (pintype "passive"))
      (node (ref "XS1") (pin "12") (pinfunction "LEDA_12") (pintype "passive"))
    )
    (net (code "53") (name "5V") (class "Default")
      (node (ref "B1") (pin "1") (pinfunction "+_1") (pintype "passive"))
      (node (ref "C18") (pin "2") (pinfunction "2_2") (pintype "passive"))
      (node (ref "C20") (pin "1") (pinfunction "1_1") (pintype "passive"))
      (node (ref "C21") (pin "1") (pinfunction "1_1") (pintype "passive"))
      (node (ref "C22") (pin "2") (pinfunction "2_2") (pintype "passive"))
      (node (ref "C24") (pin "1") (pinfunction "1_1") (pintype "passive"))
      (node (ref "CON4") (pin "1") (pinfunction "1_1") (pintype "passive"))
      (node (ref "CON8") (pin "1") (pinfunction "1_1") (pintype "passive"))
      (node (ref "D7") (pin "1") (pinfunction "VDD_1") (pintype "passive"))
      (node (ref "IC1") (pin "3") (pinfunction "VCC_3") (pintype "passive"))
      (node (ref "L2") (pin "1") (pinfunction "1_1") (pintype "passive"))
      (node (ref "P2") (pin "19") (pinfunction "19_19") (pintype "passive"))
      (node (ref "PAD4") (pin "1") (pinfunction "1_1") (pintype "passive"))
      (node (ref "R25") (pin "2") (pinfunction "2_2") (pintype "passive"))
      (node (ref "R42") (pin "1") (pinfunction "1_1") (pintype "passive"))
      (node (ref "U2") (pin "3") (pinfunction "VIN_3") (pintype "passive"))
      (node (ref "XS5") (pin "50") (pinfunction "5V_50") (pintype "passive"))
    )
    (net (code "54") (name "12V") (class "Default")
      (node (ref "12V") (pin "1") (pinfunction "1_1") (pintype "passive"))
      (node (ref "C19") (pin "2") (pinfunction "2_2") (pintype "passive"))
      (node (ref "C2") (pin "1") (pinfunction "1_1") (pintype "passive"))
      (node (ref "C3") (pin "1") (pinfunction "1_1") (pintype "passive"))
      (node (ref "C4") (pin "1") (pinfunction "1_1") (pintype "passive"))
      (node (ref "C5") (pin "1") (pinfunction "1_1") (pintype "passive"))
      (node (ref "C6") (pin "1") (pinfunction "1_1") (pintype "passive"))
      (node (ref "L1") (pin "2") (pinfunction "2_2") (pintype "passive"))
      (node (ref "P2") (pin "22") (pinfunction "22_22") (pintype "passive"))
      (node (ref "PAD1") (pin "1") (pinfunction "1_1") (pintype "passive"))
      (node (ref "R20") (pin "2") (pinfunction "2_2") (pintype "passive"))
      (node (ref "R5") (pin "2") (pinfunction "2_2") (pintype "passive"))
      (node (ref "U3") (pin "3") (pinfunction "VIN_3") (pintype "passive"))
    )
    (net (code "55") (name "A3V3") (class "Default")
      (node (ref "P2") (pin "24") (pinfunction "24_24") (pintype "passive"))
      (node (ref "XS5") (pin "49") (pinfunction "3V3_49") (pintype "passive"))
    )
    (net (code "56") (name "AGND") (class "Default")
      (node (ref "P1") (pin "13") (pinfunction "13_13") (pintype "passive"))
      (node (ref "R22") (pin "2") (pinfunction "2_2") (pintype "passive"))
      (node (ref "R24") (pin "2") (pinfunction "2_2") (pintype "passive"))
    )
    (net (code "57") (name "DCBUS") (class "Default")
      (node (ref "C7") (pin "2") (pinfunction "2_2") (pintype "passive"))
      (node (ref "P1") (pin "1") (pinfunction "1_1") (pintype "passive"))
      (node (ref "P1") (pin "10") (pinfunction "10_10") (pintype "passive"))
      (node (ref "P1") (pin "11") (pinfunction "11_11") (pintype "passive"))
      (node (ref "P1") (pin "2") (pinfunction "2_2") (pintype "passive"))
      (node (ref "P1") (pin "3") (pinfunction "3_3") (pintype "passive"))
      (node (ref "P1") (pin "4") (pinfunction "4_4") (pintype "passive"))
      (node (ref "P1") (pin "5") (pinfunction "5_5") (pintype "passive"))
      (node (ref "P1") (pin "6") (pinfunction "6_6") (pintype "passive"))
      (node (ref "P1") (pin "7") (pinfunction "7_7") (pintype "passive"))
      (node (ref "P1") (pin "8") (pinfunction "8_8") (pintype "passive"))
      (node (ref "P1") (pin "9") (pinfunction "9_9") (pintype "passive"))
      (node (ref "PAD3") (pin "1") (pinfunction "1_1") (pintype "passive"))
      (node (ref "Q1") (pin "2") (pinfunction "D_2") (pintype "passive"))
      (node (ref "R1") (pin "1") (pinfunction "1_1") (pintype "passive"))
      (node (ref "R12") (pin "2") (pinfunction "2_2") (pintype "passive"))
      (node (ref "R2") (pin "2") (pinfunction "2_2") (pintype "passive"))
      (node (ref "R45") (pin "2") (pinfunction "2_2") (pintype "passive"))
      (node (ref "U1") (pin "2") (pinfunction "VIN_2") (pintype "passive"))
    )
    (net (code "58") (name "DCBUS_IN") (class "Default")
      (node (ref "C15") (pin "2") (pinfunction "2_2") (pintype "passive"))
      (node (ref "C16") (pin "2") (pinfunction "2_2") (pintype "passive"))
      (node (ref "C9") (pin "2") (pinfunction "2_2") (pintype "passive"))
      (node (ref "D1") (pin "2") (pinfunction "2_2") (pintype "passive"))
      (node (ref "D2") (pin "2") (pinfunction "2_2") (pintype "passive"))
      (node (ref "PAD2") (pin "1") (pinfunction "1_1") (pintype "passive"))
      (node (ref "Q1") (pin "3") (pinfunction "S_3") (pintype "passive"))
      (node (ref "Q2") (pin "1") (pinfunction "E_1") (pintype "passive"))
      (node (ref "R10") (pin "2") (pinfunction "2_2") (pintype "passive"))
      (node (ref "R11") (pin "2") (pinfunction "2_2") (pintype "passive"))
      (node (ref "R17") (pin "2") (pinfunction "2_2") (pintype "passive"))
      (node (ref "S1") (pin "1") (pinfunction "+_1") (pintype "passive"))
      (node (ref "S2") (pin "1") (pinfunction "+_1") (pintype "passive"))
    )
    (net (code "59") (name "GND") (class "Default")
      (node (ref "12V") (pin "2") (pinfunction "2_2") (pintype "passive"))
      (node (ref "C17") (pin "1") (pinfunction "1_1") (pintype "passive"))
      (node (ref "C18") (pin "1") (pinfunction "1_1") (pintype "passive"))
      (node (ref "C19") (pin "1") (pinfunction "1_1") (pintype "passive"))
      (node (ref "C20") (pin "2") (pinfunction "2_2") (pintype "passive"))
      (node (ref "C21") (pin "2") (pinfunction "2_2") (pintype "passive"))
      (node (ref "C23") (pin "1") (pinfunction "1_1") (pintype "passive"))
      (node (ref "C24") (pin "2") (pinfunction "2_2") (pintype "passive"))
      (node (ref "C25") (pin "2") (pinfunction "2_2") (pintype "passive"))
      (node (ref "C26") (pin "1") (pinfunction "1_1") (pintype "passive"))
      (node (ref "C27") (pin "1") (pinfunction "1_1") (pintype "passive"))
      (node (ref "C28") (pin "1") (pinfunction "1_1") (pintype "passive"))
      (node (ref "C29") (pin "1") (pinfunction "1_1") (pintype "passive"))
      (node (ref "C3") (pin "2") (pinfunction "2_2") (pintype "passive"))
      (node (ref "C4") (pin "2") (pinfunction "2_2") (pintype "passive"))
      (node (ref "C5") (pin "2") (pinfunction "2_2") (pintype "passive"))
      (node (ref "C6") (pin "2") (pinfunction "2_2") (pintype "passive"))
      (node (ref "C7") (pin "1") (pinfunction "1_1") (pintype "passive"))
      (node (ref "CON1") (pin "0") (pinfunction "0_0") (pintype "passive"))
      (node (ref "CON10") (pin "0") (pinfunction "0_0") (pintype "passive"))
      (node (ref "CON2") (pin "0") (pinfunction "0_0") (pintype "passive"))
      (node (ref "CON3") (pin "0") (pinfunction "0_0") (pintype "passive"))
      (node (ref "CON4") (pin "0") (pinfunction "0_0") (pintype "passive"))
      (node (ref "CON4") (pin "2") (pinfunction "2_2") (pintype "passive"))
      (node (ref "CON5") (pin "0") (pinfunction "0_0") (pintype "passive"))
      (node (ref "CON5") (pin "2") (pinfunction "2_2") (pintype "passive"))
      (node (ref "CON6") (pin "0") (pinfunction "0_0") (pintype "passive"))
      (node (ref "CON7") (pin "0") (pinfunction "0_0") (pintype "passive"))
      (node (ref "CON8") (pin "0") (pinfunction "0_0") (pintype "passive"))
      (node (ref "CON8") (pin "2") (pinfunction "2_2") (pintype "passive"))
      (node (ref "CON9") (pin "0") (pinfunction "0_0") (pintype "passive"))
      (node (ref "CON9") (pin "2") (pinfunction "2_2") (pintype "passive"))
      (node (ref "D7") (pin "3") (pinfunction "GND_3") (pintype "passive"))
      (node (ref "IC1") (pin "2") (pinfunction "GND_2") (pintype "passive"))
      (node (ref "IC1") (pin "8") (pinfunction "GND_8") (pintype "passive"))
      (node (ref "K1") (pin "2") (pinfunction "2_2") (pintype "passive"))
      (node (ref "K2") (pin "2") (pinfunction "2_2") (pintype "passive"))
      (node (ref "K3") (pin "2") (pinfunction "2_2") (pintype "passive"))
      (node (ref "P1") (pin "12") (pinfunction "12_12") (pintype "passive"))
      (node (ref "Q4") (pin "2") (pinfunction "E_2") (pintype "passive"))
      (node (ref "Q5") (pin "2") (pinfunction "E_2") (pintype "passive"))
      (node (ref "R15") (pin "1") (pinfunction "1_1") (pintype "passive"))
      (node (ref "R21") (pin "2") (pinfunction "2_2") (pintype "passive"))
      (node (ref "R22") (pin "1") (pinfunction "1_1") (pintype "passive"))
      (node (ref "R23") (pin "2") (pinfunction "2_2") (pintype "passive"))
      (node (ref "R24") (pin "1") (pinfunction "1_1") (pintype "passive"))
      (node (ref "R30") (pin "1") (pinfunction "1_1") (pintype "passive"))
      (node (ref "R31") (pin "2") (pinfunction "2_2") (pintype "passive"))
      (node (ref "R32") (pin "2") (pinfunction "2_2") (pintype "passive"))
      (node (ref "R43") (pin "2") (pinfunction "2_2") (pintype "passive"))
      (node (ref "R49") (pin "1") (pinfunction "1_1") (pintype "passive"))
      (node (ref "R50") (pin "1") (pinfunction "1_1") (pintype "passive"))
      (node (ref "R9") (pin "2") (pinfunction "2_2") (pintype "passive"))
      (node (ref "U1") (pin "1") (pinfunction "GND_1") (pintype "passive"))
      (node (ref "U1") (pin "9") (pinfunction "EP_9") (pintype "passive"))
      (node (ref "U2") (pin "1") (pinfunction "GND_1") (pintype "passive"))
      (node (ref "U3") (pin "1") (pinfunction "GND_1") (pintype "passive"))
      (node (ref "U4") (pin "3") (pinfunction "3_3") (pintype "passive"))
      (node (ref "U5") (pin "3") (pinfunction "GND_3") (pintype "passive"))
      (node (ref "XS1") (pin "13") (pinfunction "GND_13") (pintype "passive"))
      (node (ref "XS1") (pin "8") (pinfunction "GND_8") (pintype "passive"))
      (node (ref "XS2") (pin "13") (pinfunction "GND_13") (pintype "passive"))
      (node (ref "XS2") (pin "14") (pinfunction "GND_14") (pintype "passive"))
      (node (ref "XS2") (pin "15") (pinfunction "GND_15") (pintype "passive"))
      (node (ref "XS2") (pin "16") (pinfunction "GND_16") (pintype "passive"))
      (node (ref "XS2") (pin "A1B12") (pinfunction "GND_A1B12") (pintype "passive"))
      (node (ref "XS2") (pin "B1A12") (pinfunction "GND_B1A12") (pintype "passive"))
      (node (ref "XS4") (pin "13") (pinfunction "GND_13") (pintype "passive"))
      (node (ref "XS4") (pin "14") (pinfunction "GND_14") (pintype "passive"))
      (node (ref "XS4") (pin "15") (pinfunction "GND_15") (pintype "passive"))
      (node (ref "XS4") (pin "16") (pinfunction "GND_16") (pintype "passive"))
      (node (ref "XS4") (pin "A1B12") (pinfunction "GND_A1B12") (pintype "passive"))
      (node (ref "XS4") (pin "B1A12") (pinfunction "GND_B1A12") (pintype "passive"))
      (node (ref "XS5") (pin "1") (pinfunction "GND_1") (pintype "passive"))
    )
    (net (code "60") (name "Net-(B1--)") (class "Default")
      (node (ref "B1") (pin "2") (pinfunction "-_2") (pintype "passive"))
      (node (ref "Q5") (pin "3") (pinfunction "C_3") (pintype "passive"))
    )
    (net (code "61") (name "Net-(C2-Pad2)") (class "Default")
      (node (ref "C2") (pin "2") (pinfunction "2_2") (pintype "passive"))
      (node (ref "C8") (pin "1") (pinfunction "1_1") (pintype "passive"))
      (node (ref "R8") (pin "1") (pinfunction "1_1") (pintype "passive"))
    )
    (net (code "62") (name "Net-(C10-Pad2)") (class "Default")
      (node (ref "C10") (pin "2") (pinfunction "2_2") (pintype "passive"))
      (node (ref "R12") (pin "1") (pinfunction "1_1") (pintype "passive"))
    )
    (net (code "63") (name "Net-(C14-Pad2)") (class "Default")
      (node (ref "C14") (pin "2") (pinfunction "2_2") (pintype "passive"))
      (node (ref "R17") (pin "1") (pinfunction "1_1") (pintype "passive"))
    )
    (net (code "64") (name "Net-(D4-Pad2)") (class "Default")
      (node (ref "D4") (pin "2") (pinfunction "2_2") (pintype "passive"))
      (node (ref "R11") (pin "1") (pinfunction "1_1") (pintype "passive"))
      (node (ref "R16") (pin "2") (pinfunction "2_2") (pintype "passive"))
    )
    (net (code "65") (name "Net-(D5-Pad1)") (class "Default")
      (node (ref "D5") (pin "1") (pintype "passive"))
      (node (ref "R34") (pin "2") (pinfunction "2_2") (pintype "passive"))
    )
    (net (code "66") (name "Net-(D8-Pad1)") (class "Default")
      (node (ref "D8") (pin "1") (pintype "passive"))
      (node (ref "R44") (pin "2") (pinfunction "2_2") (pintype "passive"))
    )
    (net (code "67") (name "Net-(Q1-G)") (class "Default")
      (node (ref "C9") (pin "1") (pinfunction "1_1") (pintype "passive"))
      (node (ref "D1") (pin "1") (pinfunction "1_1") (pintype "passive"))
      (node (ref "Q1") (pin "1") (pinfunction "G_1") (pintype "passive"))
      (node (ref "R18") (pin "2") (pinfunction "2_2") (pintype "passive"))
    )
    (net (code "68") (name "Net-(Q2-B)") (class "Default")
      (node (ref "C12") (pin "2") (pinfunction "2_2") (pintype "passive"))
      (node (ref "Q2") (pin "2") (pinfunction "B_2") (pintype "passive"))
      (node (ref "R1") (pin "2") (pinfunction "2_2") (pintype "passive"))
      (node (ref "R16") (pin "1") (pinfunction "1_1") (pintype "passive"))
    )
    (net (code "69") (name "Net-(Q2-C)") (class "Default")
      (node (ref "C12") (pin "1") (pinfunction "1_1") (pintype "passive"))
      (node (ref "Q2") (pin "3") (pinfunction "C_3") (pintype "passive"))
      (node (ref "R18") (pin "1") (pinfunction "1_1") (pintype "passive"))
      (node (ref "R19") (pin "2") (pinfunction "2_2") (pintype "passive"))
    )
    (net (code "70") (name "Net-(Q3-G)") (class "Default")
      (node (ref "C11") (pin "2") (pinfunction "2_2") (pintype "passive"))
      (node (ref "D3") (pin "2") (pinfunction "2_2") (pintype "passive"))
      (node (ref "Q3") (pin "1") (pinfunction "G_1") (pintype "passive"))
      (node (ref "R10") (pin "1") (pinfunction "1_1") (pintype "passive"))
    )
    (net (code "71") (name "Net-(Q4-B)") (class "Default")
      (node (ref "Q4") (pin "1") (pinfunction "B_1") (pintype "passive"))
      (node (ref "R38") (pin "2") (pinfunction "2_2") (pintype "passive"))
      (node (ref "R40") (pin "1") (pinfunction "1_1") (pintype "passive"))
    )
    (net (code "72") (name "Net-(Q4-C)") (class "Default")
      (node (ref "Q4") (pin "3") (pinfunction "C_3") (pintype "passive"))
      (node (ref "R39") (pin "2") (pinfunction "2_2") (pintype "passive"))
    )
    (net (code "73") (name "Net-(R3-Pad2)") (class "Default")
      (node (ref "R3") (pin "2") (pinfunction "2_2") (pintype "passive"))
      (node (ref "R4") (pin "1") (pinfunction "1_1") (pintype "passive"))
    )
    (net (code "74") (name "Net-(R4-Pad2)") (class "Default")
      (node (ref "R4") (pin "2") (pinfunction "2_2") (pintype "passive"))
      (node (ref "R5") (pin "1") (pinfunction "1_1") (pintype "passive"))
    )
    (net (code "75") (name "Net-(R6-Pad1)") (class "Default")
      (node (ref "R6") (pin "1") (pinfunction "1_1") (pintype "passive"))
      (node (ref "R7") (pin "2") (pinfunction "2_2") (pintype "passive"))
    )
    (net (code "76") (name "Net-(R7-Pad1)") (class "Default")
      (node (ref "R7") (pin "1") (pinfunction "1_1") (pintype "passive"))
      (node (ref "R8") (pin "2") (pinfunction "2_2") (pintype "passive"))
    )
    (net (code "77") (name "Net-(R13-Pad1)") (class "Default")
      (node (ref "R13") (pin "1") (pinfunction "1_1") (pintype "passive"))
      (node (ref "R14") (pin "2") (pinfunction "2_2") (pintype "passive"))
    )
    (net (code "78") (name "Net-(R14-Pad1)") (class "Default")
      (node (ref "R14") (pin "1") (pinfunction "1_1") (pintype "passive"))
      (node (ref "R15") (pin "2") (pinfunction "2_2") (pintype "passive"))
    )
    (net (code "79") (name "Net-(R25-Pad1)") (class "Default")
      (node (ref "R25") (pin "1") (pinfunction "1_1") (pintype "passive"))
      (node (ref "R26") (pin "2") (pinfunction "2_2") (pintype "passive"))
    )
    (net (code "80") (name "Net-(R26-Pad1)") (class "Default")
      (node (ref "R26") (pin "1") (pinfunction "1_1") (pintype "passive"))
      (node (ref "R27") (pin "2") (pinfunction "2_2") (pintype "passive"))
    )
    (net (code "81") (name "Net-(R28-Pad1)") (class "Default")
      (node (ref "R28") (pin "1") (pinfunction "1_1") (pintype "passive"))
      (node (ref "R29") (pin "2") (pinfunction "2_2") (pintype "passive"))
    )
    (net (code "82") (name "Net-(R29-Pad1)") (class "Default")
      (node (ref "R29") (pin "1") (pinfunction "1_1") (pintype "passive"))
      (node (ref "R30") (pin "2") (pinfunction "2_2") (pintype "passive"))
    )
    (net (code "83") (name "Net-(R33-Pad1)") (class "Default")
      (node (ref "R33") (pin "1") (pinfunction "1_1") (pintype "passive"))
      (node (ref "R35") (pin "1") (pinfunction "1_1") (pintype "passive"))
    )
    (net (code "84") (name "Net-(R34-Pad1)") (class "Default")
      (node (ref "R34") (pin "1") (pinfunction "1_1") (pintype "passive"))
      (node (ref "XS2") (pin "A4B9") (pinfunction "VBUS_A4B9") (pintype "passive"))
      (node (ref "XS2") (pin "B4A9") (pinfunction "VBUS_B4A9") (pintype "passive"))
    )
    (net (code "85") (name "Net-(R44-Pad1)") (class "Default")
      (node (ref "R44") (pin "1") (pinfunction "1_1") (pintype "passive"))
      (node (ref "XS4") (pin "A4B9") (pinfunction "VBUS_A4B9") (pintype "passive"))
      (node (ref "XS4") (pin "B4A9") (pinfunction "VBUS_B4A9") (pintype "passive"))
    )
    (net (code "86") (name "Net-(U1-BST)") (class "Default")
      (node (ref "C1") (pin "2") (pinfunction "2_2") (pintype "passive"))
      (node (ref "U1") (pin "7") (pinfunction "BST_7") (pintype "passive"))
    )
    (net (code "87") (name "Net-(U1-EN{slash}UVLO)") (class "Default")
      (node (ref "R2") (pin "1") (pinfunction "1_1") (pintype "passive"))
      (node (ref "U1") (pin "3") (pinfunction "EN/UVLO_3") (pintype "passive"))
    )
    (net (code "88") (name "Net-(U1-FB)") (class "Default")
      (node (ref "C8") (pin "2") (pinfunction "2_2") (pintype "passive"))
      (node (ref "R13") (pin "2") (pinfunction "2_2") (pintype "passive"))
      (node (ref "R3") (pin "1") (pinfunction "1_1") (pintype "passive"))
      (node (ref "U1") (pin "5") (pinfunction "FB_5") (pintype "passive"))
    )
    (net (code "89") (name "Net-(U1-RON)") (class "Default")
      (node (ref "R9") (pin "1") (pinfunction "1_1") (pintype "passive"))
      (node (ref "U1") (pin "4") (pinfunction "RON_4") (pintype "passive"))
    )
    (net (code "90") (name "Net-(U1-SW)") (class "Default")
      (node (ref "C1") (pin "1") (pinfunction "1_1") (pintype "passive"))
      (node (ref "L1") (pin "1") (pinfunction "1_1") (pintype "passive"))
      (node (ref "R6") (pin "2") (pinfunction "2_2") (pintype "passive"))
      (node (ref "U1") (pin "8") (pinfunction "SW_8") (pintype "passive"))
    )
    (net (code "91") (name "Net-(U3-BOOT)") (class "Default")
      (node (ref "C13") (pin "1") (pinfunction "1_1") (pintype "passive"))
      (node (ref "U3") (pin "6") (pinfunction "BOOT_6") (pintype "passive"))
    )
    (net (code "92") (name "Net-(U3-ED)") (class "Default")
      (node (ref "R20") (pin "1") (pinfunction "1_1") (pintype "passive"))
      (node (ref "U3") (pin "5") (pinfunction "ED_5") (pintype "passive"))
    )
    (net (code "93") (name "Net-(U3-FB)") (class "Default")
      (node (ref "C22") (pin "1") (pinfunction "1_1") (pintype "passive"))
      (node (ref "R27") (pin "1") (pinfunction "1_1") (pintype "passive"))
      (node (ref "R28") (pin "2") (pinfunction "2_2") (pintype "passive"))
      (node (ref "U3") (pin "4") (pinfunction "FB_4") (pintype "passive"))
    )
    (net (code "94") (name "Net-(U3-SW)") (class "Default")
      (node (ref "C13") (pin "2") (pinfunction "2_2") (pintype "passive"))
      (node (ref "L2") (pin "2") (pinfunction "2_2") (pintype "passive"))
      (node (ref "U3") (pin "2") (pinfunction "SW_2") (pintype "passive"))
    )
    (net (code "95") (name "Net-(U5-RXD)") (class "Default")
      (node (ref "R41") (pin "1") (pinfunction "1_1") (pintype "passive"))
      (node (ref "U5") (pin "9") (pinfunction "RXD_9") (pintype "passive"))
    )
    (net (code "96") (name "Net-(U5-TXD)") (class "Default")
      (node (ref "D6") (pin "2") (pintype "passive"))
      (node (ref "U5") (pin "8") (pinfunction "TXD_8") (pintype "passive"))
    )
    (net (code "97") (name "Net-(U5-V3)") (class "Default")
      (node (ref "C25") (pin "1") (pinfunction "1_1") (pintype "passive"))
      (node (ref "U5") (pin "10") (pinfunction "V3_10") (pintype "passive"))
    )
    (net (code "98") (name "Net-(XS1-LEDK)") (class "Default")
      (node (ref "R39") (pin "1") (pinfunction "1_1") (pintype "passive"))
      (node (ref "XS1") (pin "11") (pinfunction "LEDK_11") (pintype "passive"))
    )
    (net (code "99") (name "Net-(XS2-CC1)") (class "Default")
      (node (ref "R32") (pin "1") (pinfunction "1_1") (pintype "passive"))
      (node (ref "XS2") (pin "A5") (pinfunction "CC1_A5") (pintype "passive"))
    )
    (net (code "100") (name "Net-(XS2-CC2)") (class "Default")
      (node (ref "R31") (pin "1") (pinfunction "1_1") (pintype "passive"))
      (node (ref "XS2") (pin "B5") (pinfunction "CC2_B5") (pintype "passive"))
    )
    (net (code "101") (name "Net-(XS2-DN1)") (class "Default")
      (node (ref "R37") (pin "2") (pinfunction "2_2") (pintype "passive"))
      (node (ref "XS2") (pin "A7") (pinfunction "DN1_A7") (pintype "passive"))
      (node (ref "XS2") (pin "B7") (pinfunction "DN2_B7") (pintype "passive"))
    )
    (net (code "102") (name "Net-(XS2-DP1)") (class "Default")
      (node (ref "R36") (pin "2") (pinfunction "2_2") (pintype "passive"))
      (node (ref "XS2") (pin "A6") (pinfunction "DP1_A6") (pintype "passive"))
      (node (ref "XS2") (pin "B6") (pinfunction "DP2_B6") (pintype "passive"))
    )
    (net (code "103") (name "PGND") (class "Default")
      (node (ref "C10") (pin "1") (pinfunction "1_1") (pintype "passive"))
      (node (ref "C11") (pin "1") (pinfunction "1_1") (pintype "passive"))
      (node (ref "D3") (pin "1") (pinfunction "1_1") (pintype "passive"))
      (node (ref "P1") (pin "14") (pinfunction "14_14") (pintype "passive"))
      (node (ref "P1") (pin "15") (pinfunction "15_15") (pintype "passive"))
      (node (ref "P1") (pin "16") (pinfunction "16_16") (pintype "passive"))
      (node (ref "P1") (pin "17") (pinfunction "17_17") (pintype "passive"))
      (node (ref "P1") (pin "18") (pinfunction "18_18") (pintype "passive"))
      (node (ref "P1") (pin "19") (pinfunction "19_19") (pintype "passive"))
      (node (ref "P1") (pin "20") (pinfunction "20_20") (pintype "passive"))
      (node (ref "P1") (pin "21") (pinfunction "21_21") (pintype "passive"))
      (node (ref "P1") (pin "22") (pinfunction "22_22") (pintype "passive"))
      (node (ref "P1") (pin "23") (pinfunction "23_23") (pintype "passive"))
      (node (ref "P1") (pin "24") (pinfunction "24_24") (pintype "passive"))
      (node (ref "Q3") (pin "3") (pinfunction "S_3") (pintype "passive"))
      (node (ref "R19") (pin "1") (pinfunction "1_1") (pintype "passive"))
      (node (ref "R21") (pin "1") (pinfunction "1_1") (pintype "passive"))
      (node (ref "R23") (pin "1") (pinfunction "1_1") (pintype "passive"))
    )
    (net (code "104") (name "PGND_IN") (class "Default")
      (node (ref "C14") (pin "1") (pinfunction "1_1") (pintype "passive"))
      (node (ref "C15") (pin "1") (pinfunction "1_1") (pintype "passive"))
      (node (ref "C16") (pin "1") (pinfunction "1_1") (pintype "passive"))
      (node (ref "D2") (pin "1") (pinfunction "1_1") (pintype "passive"))
      (node (ref "D4") (pin "1") (pinfunction "1_1") (pintype "passive"))
      (node (ref "Q3") (pin "2") (pinfunction "D_2") (pintype "passive"))
      (node (ref "S1") (pin "2") (pinfunction "-_2") (pintype "passive"))
      (node (ref "S2") (pin "2") (pinfunction "-_2") (pintype "passive"))
    )
    (net (code "105") (name "USB_5V") (class "Default")
      (node (ref "C26") (pin "2") (pinfunction "2_2") (pintype "passive"))
      (node (ref "C27") (pin "2") (pinfunction "2_2") (pintype "passive"))
      (node (ref "D5") (pin "2") (pintype "passive"))
      (node (ref "D8") (pin "2") (pintype "passive"))
      (node (ref "R42") (pin "2") (pinfunction "2_2") (pintype "passive"))
      (node (ref "U5") (pin "7") (pinfunction "VCC_7") (pintype "passive"))
    )
    (net (code "106") (name "unconnected-(D7-DOUT-Pad2)") (class "Default")
      (node (ref "D7") (pin "2") (pinfunction "DOUT_2") (pintype "passive+no_connect"))
    )
    (net (code "107") (name "unconnected-(IC1-VREF-Pad5)") (class "Default")
      (node (ref "IC1") (pin "5") (pinfunction "VREF_5") (pintype "passive+no_connect"))
    )
    (net (code "108") (name "unconnected-(P2-Pad23)") (class "Default")
      (node (ref "P2") (pin "23") (pinfunction "23_23") (pintype "passive+no_connect"))
    )
    (net (code "109") (name "unconnected-(U1-PGOOD-Pad6)") (class "Default")
      (node (ref "U1") (pin "6") (pinfunction "PGOOD_6") (pintype "passive+no_connect"))
    )
    (net (code "110") (name "unconnected-(U5-CTS#-Pad5)") (class "Default")
      (node (ref "U5") (pin "5") (pinfunction "CTS#_5") (pintype "passive+no_connect"))
    )
    (net (code "111") (name "unconnected-(U5-RTS#-Pad4)") (class "Default")
      (node (ref "U5") (pin "4") (pinfunction "RTS#_4") (pintype "passive+no_connect"))
    )
    (net (code "112") (name "unconnected-(U5-TNOW-Pad6)") (class "Default")
      (node (ref "U5") (pin "6") (pinfunction "TNOW_6") (pintype "passive+no_connect"))
    )
    (net (code "113") (name "unconnected-(XS1-NC-Pad9)") (class "Default")
      (node (ref "XS1") (pin "9") (pinfunction "NC_9") (pintype "passive+no_connect"))
    )
    (net (code "114") (name "unconnected-(XS1-TP0-Pad1)") (class "Default")
      (node (ref "XS1") (pin "1") (pinfunction "TP0_1") (pintype "passive+no_connect"))
    )
    (net (code "115") (name "unconnected-(XS1-TP1-Pad2)") (class "Default")
      (node (ref "XS1") (pin "2") (pinfunction "TP1_2") (pintype "passive+no_connect"))
    )
    (net (code "116") (name "unconnected-(XS2-SBU1-PadA8)") (class "Default")
      (node (ref "XS2") (pin "A8") (pinfunction "SBU1_A8") (pintype "passive"))
    )
    (net (code "117") (name "unconnected-(XS2-SBU2-PadB8)") (class "Default")
      (node (ref "XS2") (pin "B8") (pinfunction "SBU2_B8") (pintype "passive"))
    )
    (net (code "118") (name "unconnected-(XS4-CC1-PadA5)") (class "Default")
      (node (ref "XS4") (pin "A5") (pinfunction "CC1_A5") (pintype "passive"))
    )
    (net (code "119") (name "unconnected-(XS4-CC2-PadB5)") (class "Default")
      (node (ref "XS4") (pin "B5") (pinfunction "CC2_B5") (pintype "passive"))
    )
    (net (code "120") (name "unconnected-(XS4-SBU1-PadA8)") (class "Default")
      (node (ref "XS4") (pin "A8") (pinfunction "SBU1_A8") (pintype "passive"))
    )
    (net (code "121") (name "unconnected-(XS4-SBU2-PadB8)") (class "Default")
      (node (ref "XS4") (pin "B8") (pinfunction "SBU2_B8") (pintype "passive"))
    )
  )
)
